# serialconnection.net
KiCad netlist of a schematic drawn in EAGLE
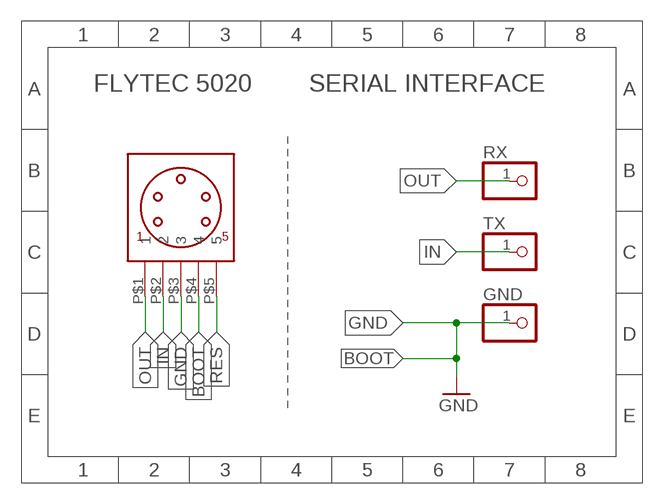
[diagram p0: schematic, sheet 1]

(export (version "E")
  (design (tool "Eeschema 10.0.6"))
  (components
    (comp (ref "GND")
      (value "PINHD-1X1")
      (footprint "eagle-import:1X01")
      (libsource (lib "eagle-import") (part "PINHD-1X1"))
    )
    (comp (ref "RX")
      (value "PINHD-1X1")
      (footprint "eagle-import:1X01")
      (libsource (lib "eagle-import") (part "PINHD-1X1"))
    )
    (comp (ref "TX")
      (value "PINHD-1X1")
      (footprint "eagle-import:1X01")
      (libsource (lib "eagle-import") (part "PINHD-1X1"))
    )
    (comp (ref "U$1")
      (value "SERIAL_CONNECTOR")
      (footprint "eagle-import:SERIAL_CONNECTOR")
      (libsource (lib "eagle-import") (part "SERIAL_CONNECTOR"))
    )
  )
  (nets
    (net (code "1") (name "BOOT") (class "Default")
      (node (ref "U$1") (pin "P$4") (pinfunction "4_P$4") (pintype "bidirectional"))
    )
    (net (code "2") (name "GND") (class "Default")
      (node (ref "GND") (pin "1") (pinfunction "1_1") (pintype "passive"))
      (node (ref "U$1") (pin "P$3") (pinfunction "3_P$3") (pintype "bidirectional"))
    )
    (net (code "3") (name "IN") (class "Default")
      (node (ref "TX") (pin "1") (pinfunction "1_1") (pintype "passive"))
      (node (ref "U$1") (pin "P$2") (pinfunction "2_P$2") (pintype "bidirectional"))
    )
    (net (code "4") (name "OUT") (class "Default")
      (node (ref "RX") (pin "1") (pinfunction "1_1") (pintype "passive"))
      (node (ref "U$1") (pin "P$1") (pinfunction "1_P$1") (pintype "bidirectional"))
    )
    (net (code "5") (name "RES") (class "Default")
      (node (ref "U$1") (pin "P$5") (pinfunction "5_P$5") (pintype "bidirectional"))
    )
  )
)
